# TwoMotorController_2_0.net
KiCad netlist of a schematic drawn in EAGLE
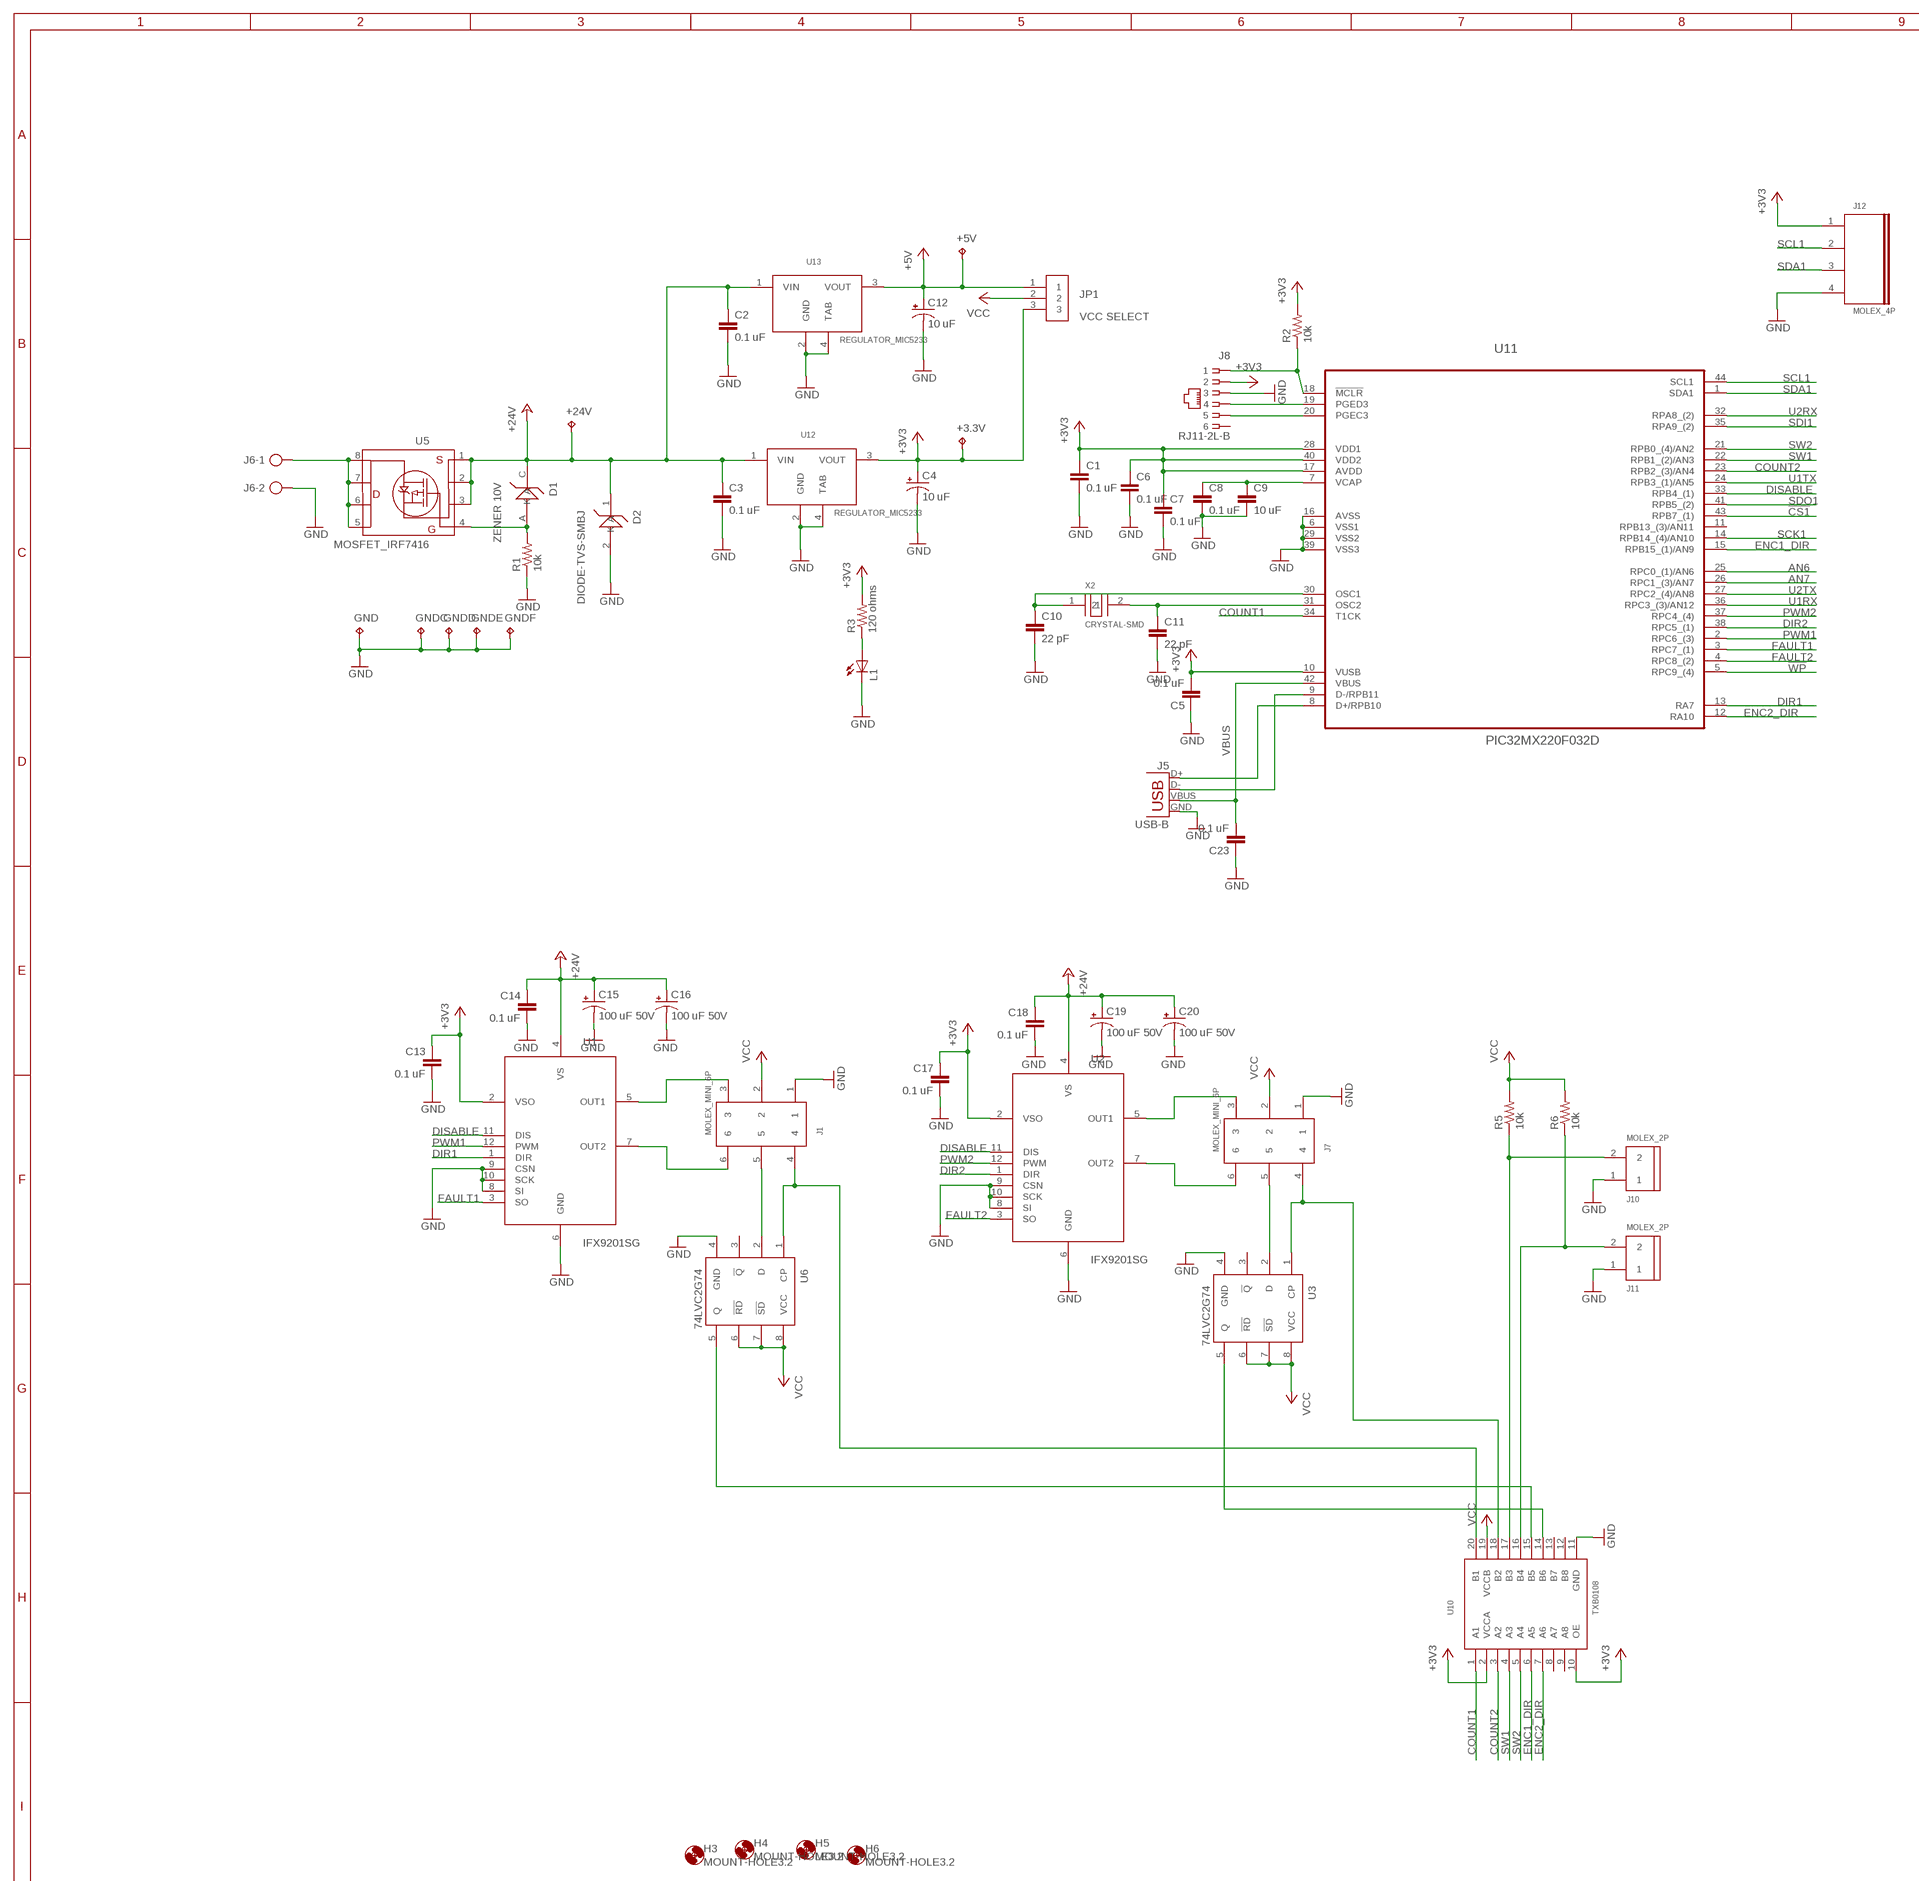
[diagram p0: schematic, sheet 1, part 1 of 2]
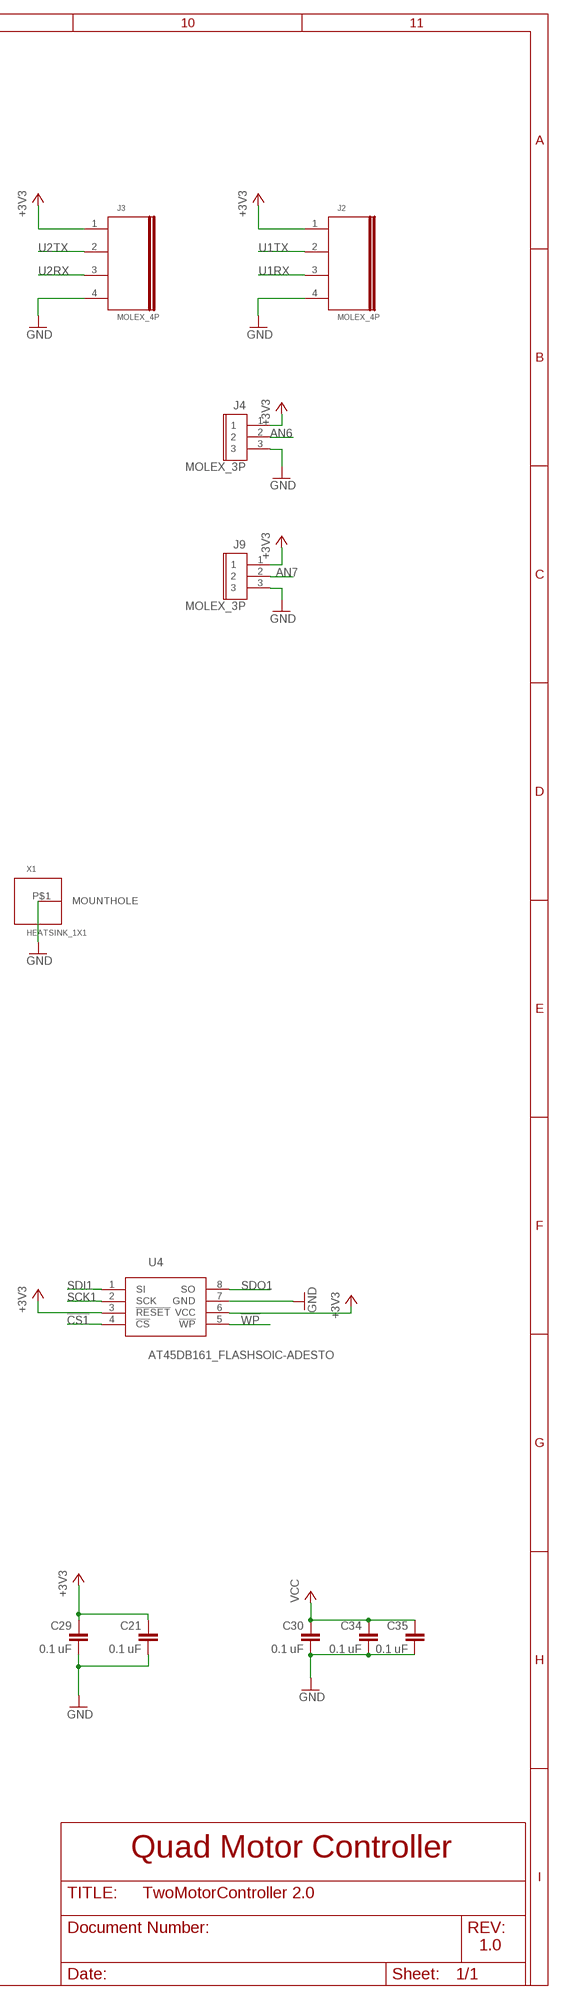
[diagram p1: schematic, sheet 1, part 2 of 2]

(export (version "E")
  (design (tool "Eeschema 10.0.6"))
  (components
    (comp (ref "+3.3V")
      (value "TP")
      (footprint "eagle-import:TESTPAD")
      (libsource (lib "eagle-import") (part "TP"))
    )
    (comp (ref "+5V")
      (value "TP")
      (footprint "eagle-import:TESTPAD")
      (libsource (lib "eagle-import") (part "TP"))
    )
    (comp (ref "+24V")
      (value "TP")
      (footprint "eagle-import:TESTPAD")
      (libsource (lib "eagle-import") (part "TP"))
    )
    (comp (ref "C1")
      (value "0.1 uF")
      (footprint "eagle-import:C0805")
      (libsource (lib "eagle-import") (part "C0805"))
    )
    (comp (ref "C2")
      (value "0.1 uF")
      (footprint "eagle-import:C0805")
      (libsource (lib "eagle-import") (part "C0805"))
    )
    (comp (ref "C3")
      (value "0.1 uF")
      (footprint "eagle-import:C0805")
      (libsource (lib "eagle-import") (part "C0805"))
    )
    (comp (ref "C4")
      (value "10 uF")
      (footprint "eagle-import:POLCAP_2MM")
      (libsource (lib "eagle-import") (part "POLCAPE2-5"))
    )
    (comp (ref "C5")
      (value "0.1 uF")
      (footprint "eagle-import:C2.5-3")
      (libsource (lib "eagle-import") (part "C2,5-3"))
    )
    (comp (ref "C6")
      (value "0.1 uF")
      (footprint "eagle-import:C0805")
      (libsource (lib "eagle-import") (part "C0805"))
    )
    (comp (ref "C7")
      (value "0.1 uF")
      (footprint "eagle-import:C0805")
      (libsource (lib "eagle-import") (part "C0805"))
    )
    (comp (ref "C8")
      (value "0.1 uF")
      (footprint "eagle-import:C0805")
      (libsource (lib "eagle-import") (part "C0805"))
    )
    (comp (ref "C9")
      (value "10 uF")
      (footprint "eagle-import:C0805")
      (libsource (lib "eagle-import") (part "C0805"))
    )
    (comp (ref "C10")
      (value "22 pF")
      (footprint "eagle-import:C0805")
      (libsource (lib "eagle-import") (part "C0805"))
    )
    (comp (ref "C11")
      (value "22 pF")
      (footprint "eagle-import:C0805")
      (libsource (lib "eagle-import") (part "C0805"))
    )
    (comp (ref "C12")
      (value "10 uF")
      (footprint "eagle-import:POLCAP_2MM")
      (libsource (lib "eagle-import") (part "POLCAPE2-5"))
    )
    (comp (ref "C13")
      (value "0.1 uF")
      (footprint "eagle-import:C0805")
      (libsource (lib "eagle-import") (part "C0805"))
    )
    (comp (ref "C14")
      (value "0.1 uF")
      (footprint "eagle-import:C0805")
      (libsource (lib "eagle-import") (part "C0805"))
    )
    (comp (ref "C15")
      (value "100 uF 50V")
      (footprint "eagle-import:E3,5-10")
      (libsource (lib "eagle-import") (part "POLCAPE3.5-10"))
    )
    (comp (ref "C16")
      (value "100 uF 50V")
      (footprint "eagle-import:E3,5-10")
      (libsource (lib "eagle-import") (part "POLCAPE3.5-10"))
    )
    (comp (ref "C17")
      (value "0.1 uF")
      (footprint "eagle-import:C0805")
      (libsource (lib "eagle-import") (part "C0805"))
    )
    (comp (ref "C18")
      (value "0.1 uF")
      (footprint "eagle-import:C0805")
      (libsource (lib "eagle-import") (part "C0805"))
    )
    (comp (ref "C19")
      (value "100 uF 50V")
      (footprint "eagle-import:E3,5-10")
      (libsource (lib "eagle-import") (part "POLCAPE3.5-10"))
    )
    (comp (ref "C20")
      (value "100 uF 50V")
      (footprint "eagle-import:E3,5-10")
      (libsource (lib "eagle-import") (part "POLCAPE3.5-10"))
    )
    (comp (ref "C21")
      (value "0.1 uF")
      (footprint "eagle-import:C0805")
      (libsource (lib "eagle-import") (part "C0805"))
    )
    (comp (ref "C23")
      (value "0.1 uF")
      (footprint "eagle-import:C2.5-3")
      (libsource (lib "eagle-import") (part "C2,5-3"))
    )
    (comp (ref "C29")
      (value "0.1 uF")
      (footprint "eagle-import:C0805")
      (libsource (lib "eagle-import") (part "C0805"))
    )
    (comp (ref "C30")
      (value "0.1 uF")
      (footprint "eagle-import:C0805")
      (libsource (lib "eagle-import") (part "C0805"))
    )
    (comp (ref "C34")
      (value "0.1 uF")
      (footprint "eagle-import:C0805")
      (libsource (lib "eagle-import") (part "C0805"))
    )
    (comp (ref "C35")
      (value "0.1 uF")
      (footprint "eagle-import:C0805")
      (libsource (lib "eagle-import") (part "C0805"))
    )
    (comp (ref "D1")
      (value "ZENER 10V")
      (footprint "eagle-import:DO-214AC")
      (libsource (lib "eagle-import") (part "DIODE-ZENERDO-214AC"))
    )
    (comp (ref "D2")
      (value "DIODE-TVS-SMBJ")
      (footprint "eagle-import:DIODE-TVS-SMBJ")
      (libsource (lib "eagle-import") (part "DIODE-TVS-SMBJ"))
    )
    (comp (ref "GND")
      (value "TP")
      (footprint "eagle-import:TESTPAD")
      (libsource (lib "eagle-import") (part "TP"))
    )
    (comp (ref "GNDC")
      (value "TP")
      (footprint "eagle-import:TESTPAD")
      (libsource (lib "eagle-import") (part "TP"))
    )
    (comp (ref "GNDD")
      (value "TP")
      (footprint "eagle-import:TESTPAD")
      (libsource (lib "eagle-import") (part "TP"))
    )
    (comp (ref "GNDE")
      (value "TP")
      (footprint "eagle-import:TESTPAD")
      (libsource (lib "eagle-import") (part "TP"))
    )
    (comp (ref "GNDF")
      (value "TP")
      (footprint "eagle-import:TESTPAD")
      (libsource (lib "eagle-import") (part "TP"))
    )
    (comp (ref "H3")
      (value "MOUNT-HOLE3.2")
      (footprint "eagle-import:3,2")
      (libsource (lib "eagle-import") (part "MOUNT-HOLE3.2"))
    )
    (comp (ref "H4")
      (value "MOUNT-HOLE3.2")
      (footprint "eagle-import:3,2")
      (libsource (lib "eagle-import") (part "MOUNT-HOLE3.2"))
    )
    (comp (ref "H5")
      (value "MOUNT-HOLE3.2")
      (footprint "eagle-import:3,2")
      (libsource (lib "eagle-import") (part "MOUNT-HOLE3.2"))
    )
    (comp (ref "H6")
      (value "MOUNT-HOLE3.2")
      (footprint "eagle-import:3,2")
      (libsource (lib "eagle-import") (part "MOUNT-HOLE3.2"))
    )
    (comp (ref "J1")
      (value "MOLEX_MINI_6P")
      (footprint "eagle-import:MOLEX_MINI_6P")
      (libsource (lib "eagle-import") (part "MOLEX_MINI_6P"))
    )
    (comp (ref "J2")
      (value "MOLEX_4P")
      (footprint "eagle-import:MOLEX_4P")
      (libsource (lib "eagle-import") (part "MOLEX_4P"))
    )
    (comp (ref "J3")
      (value "MOLEX_4P")
      (footprint "eagle-import:MOLEX_4P")
      (libsource (lib "eagle-import") (part "MOLEX_4P"))
    )
    (comp (ref "J4")
      (value "MOLEX_3P")
      (footprint "eagle-import:MOLEX_3P")
      (libsource (lib "eagle-import") (part "MOLEX_3P"))
    )
    (comp (ref "J5")
      (value "USB-B")
      (footprint "eagle-import:USB-B-PTH")
      (libsource (lib "eagle-import") (part "USBPTH"))
    )
    (comp (ref "J6")
      (value "TRMBLOCK_5MM_2P")
      (footprint "eagle-import:TRMBLOCK_5MM_2P")
      (libsource (lib "eagle-import") (part "TRMBLOCK_5MM_2P"))
    )
    (comp (ref "J7")
      (value "MOLEX_MINI_6P")
      (footprint "eagle-import:MOLEX_MINI_6P")
      (libsource (lib "eagle-import") (part "MOLEX_MINI_6P"))
    )
    (comp (ref "J8")
      (value "RJ11-2L-B")
      (footprint "eagle-import:RJ11-NO_SHIELD")
      (fields (field (name "MF") "TYCO ELECTRONICS"))
      (libsource (lib "eagle-import") (part "RJ11-2L-B"))
    )
    (comp (ref "J9")
      (value "MOLEX_3P")
      (footprint "eagle-import:MOLEX_3P")
      (libsource (lib "eagle-import") (part "MOLEX_3P"))
    )
    (comp (ref "J10")
      (value "MOLEX_2P")
      (footprint "eagle-import:MOLEX_2P")
      (libsource (lib "eagle-import") (part "MOLEX_2P"))
    )
    (comp (ref "J11")
      (value "MOLEX_2P")
      (footprint "eagle-import:MOLEX_2P")
      (libsource (lib "eagle-import") (part "MOLEX_2P"))
    )
    (comp (ref "J12")
      (value "MOLEX_4P")
      (footprint "eagle-import:MOLEX_4P")
      (libsource (lib "eagle-import") (part "MOLEX_4P"))
    )
    (comp (ref "JP1")
      (value "VCC SELECT")
      (footprint "eagle-import:JUMPER_3P")
      (libsource (lib "eagle-import") (part "JUMPER_3P"))
    )
    (comp (ref "L1")
      (value "LED5MM")
      (footprint "eagle-import:LED5MM")
      (libsource (lib "eagle-import") (part "LED5MM"))
    )
    (comp (ref "R1")
      (value "10k")
      (footprint "eagle-import:R0805")
      (libsource (lib "eagle-import") (part "RESISTORR0805"))
    )
    (comp (ref "R2")
      (value "10k")
      (footprint "eagle-import:R0805")
      (libsource (lib "eagle-import") (part "RESISTORR0805"))
    )
    (comp (ref "R3")
      (value "120 ohms")
      (footprint "eagle-import:R0805")
      (libsource (lib "eagle-import") (part "RESISTORR0805"))
    )
    (comp (ref "R5")
      (value "10k")
      (footprint "eagle-import:R0805")
      (libsource (lib "eagle-import") (part "RESISTORR0805"))
    )
    (comp (ref "R6")
      (value "10k")
      (footprint "eagle-import:R0805")
      (libsource (lib "eagle-import") (part "RESISTORR0805"))
    )
    (comp (ref "U1")
      (value "IFX9201SG")
      (footprint "eagle-import:IFX9201SG")
      (libsource (lib "eagle-import") (part "IFX9201SG"))
    )
    (comp (ref "U2")
      (value "IFX9201SG")
      (footprint "eagle-import:IFX9201SG")
      (libsource (lib "eagle-import") (part "IFX9201SG"))
    )
    (comp (ref "U3")
      (value "74LVC2G74")
      (footprint "eagle-import:TSSOP8")
      (libsource (lib "eagle-import") (part "74LVC2G74"))
    )
    (comp (ref "U4")
      (value "AT45DB161_FLASHSOIC-ADESTO")
      (footprint "eagle-import:SOIC-ADESTO")
      (libsource (lib "eagle-import") (part "AT45DB161_FLASHSOIC-ADESTO"))
    )
    (comp (ref "U5")
      (value "MOSFET_IRF7416")
      (footprint "eagle-import:SO-8-3.9MM")
      (libsource (lib "eagle-import") (part "MOSFET_IRF7416"))
    )
    (comp (ref "U6")
      (value "74LVC2G74")
      (footprint "eagle-import:TSSOP8")
      (libsource (lib "eagle-import") (part "74LVC2G74"))
    )
    (comp (ref "U10")
      (value "TXB0108")
      (footprint "eagle-import:TSSOP20")
      (libsource (lib "eagle-import") (part "TXB0108"))
    )
    (comp (ref "U11")
      (value "PIC32MX220F032D")
      (footprint "eagle-import:QFP80P1200X1200X120-44N")
      (fields (field (name "MPN") "PIC18F4550-I/PT"))
      (libsource (lib "eagle-import") (part "PIC32MX220F032D"))
    )
    (comp (ref "U12")
      (value "REGULATOR_MIC5233")
      (footprint "eagle-import:REGULATOR_MIC5233")
      (libsource (lib "eagle-import") (part "REGULATOR_MIC5233"))
    )
    (comp (ref "U13")
      (value "REGULATOR_MIC5233")
      (footprint "eagle-import:REGULATOR_MIC5233")
      (libsource (lib "eagle-import") (part "REGULATOR_MIC5233"))
    )
    (comp (ref "X1")
      (value "HEATSINK_1X1")
      (footprint "eagle-import:HEATSINK_1X1")
      (libsource (lib "eagle-import") (part "HEATSINK_1X1"))
    )
    (comp (ref "X2")
      (value "CRYSTAL-SMD")
      (footprint "eagle-import:CRYSTAL-SMD")
      (libsource (lib "eagle-import") (part "CRYSTAL-SMD"))
    )
  )
  (nets
    (net (code "1") (name "+3V3") (class "Default")
      (node (ref "+3.3V") (pin "P$1") (pinfunction "TP_P$1") (pintype "input"))
      (node (ref "C1") (pin "1") (pinfunction "1_1") (pintype "passive"))
      (node (ref "C13") (pin "1") (pinfunction "1_1") (pintype "passive"))
      (node (ref "C17") (pin "1") (pinfunction "1_1") (pintype "passive"))
      (node (ref "C21") (pin "1") (pinfunction "1_1") (pintype "passive"))
      (node (ref "C29") (pin "1") (pinfunction "1_1") (pintype "passive"))
      (node (ref "C4") (pin "+") (pinfunction "+_+") (pintype "passive"))
      (node (ref "C5") (pin "2") (pinfunction "2_2") (pintype "passive"))
      (node (ref "C6") (pin "1") (pinfunction "1_1") (pintype "passive"))
      (node (ref "C7") (pin "1") (pinfunction "1_1") (pintype "passive"))
      (node (ref "J12") (pin "1") (pinfunction "1_1") (pintype "bidirectional"))
      (node (ref "J2") (pin "1") (pinfunction "1_1") (pintype "bidirectional"))
      (node (ref "J3") (pin "1") (pinfunction "1_1") (pintype "bidirectional"))
      (node (ref "J4") (pin "1") (pinfunction "1_1") (pintype "bidirectional"))
      (node (ref "J8") (pin "2") (pinfunction "2_2") (pintype "passive"))
      (node (ref "J9") (pin "1") (pinfunction "1_1") (pintype "bidirectional"))
      (node (ref "JP1") (pin "3") (pinfunction "3_3") (pintype "bidirectional"))
      (node (ref "R2") (pin "2") (pinfunction "2_2") (pintype "passive"))
      (node (ref "R3") (pin "2") (pinfunction "2_2") (pintype "passive"))
      (node (ref "U1") (pin "2") (pinfunction "VSO_2") (pintype "bidirectional"))
      (node (ref "U10") (pin "10") (pinfunction "OE_10") (pintype "bidirectional"))
      (node (ref "U10") (pin "2") (pinfunction "VCCA_2") (pintype "bidirectional"))
      (node (ref "U11") (pin "10") (pinfunction "VUSB_10") (pintype "bidirectional"))
      (node (ref "U11") (pin "17") (pinfunction "AVDD_17") (pintype "power_in"))
      (node (ref "U11") (pin "28") (pinfunction "VDD1_28") (pintype "power_in"))
      (node (ref "U11") (pin "40") (pinfunction "VDD2_40") (pintype "input"))
      (node (ref "U12") (pin "3") (pinfunction "VOUT_3") (pintype "power_in"))
      (node (ref "U2") (pin "2") (pinfunction "VSO_2") (pintype "bidirectional"))
      (node (ref "U4") (pin "3") (pinfunction "~{RESET}_3") (pintype "input"))
      (node (ref "U4") (pin "6") (pinfunction "VCC_6") (pintype "power_in"))
    )
    (net (code "2") (name "+5V") (class "Default")
      (node (ref "+5V") (pin "P$1") (pinfunction "TP_P$1") (pintype "input"))
      (node (ref "C12") (pin "+") (pinfunction "+_+") (pintype "passive"))
      (node (ref "JP1") (pin "1") (pinfunction "1_1") (pintype "bidirectional"))
      (node (ref "U13") (pin "3") (pinfunction "VOUT_3") (pintype "power_in"))
    )
    (net (code "3") (name "+24V") (class "Default")
      (node (ref "+24V") (pin "P$1") (pinfunction "TP_P$1") (pintype "input"))
      (node (ref "C14") (pin "1") (pinfunction "1_1") (pintype "passive"))
      (node (ref "C15") (pin "+") (pinfunction "+_+") (pintype "passive"))
      (node (ref "C16") (pin "+") (pinfunction "+_+") (pintype "passive"))
      (node (ref "C18") (pin "1") (pinfunction "1_1") (pintype "passive"))
      (node (ref "C19") (pin "+") (pinfunction "+_+") (pintype "passive"))
      (node (ref "C2") (pin "1") (pinfunction "1_1") (pintype "passive"))
      (node (ref "C20") (pin "+") (pinfunction "+_+") (pintype "passive"))
      (node (ref "C3") (pin "1") (pinfunction "1_1") (pintype "passive"))
      (node (ref "D1") (pin "C") (pinfunction "K_C") (pintype "power_in"))
      (node (ref "D2") (pin "1") (pinfunction "K_1") (pintype "power_in"))
      (node (ref "U1") (pin "4") (pinfunction "VS_4") (pintype "power_in"))
      (node (ref "U12") (pin "1") (pinfunction "VIN_1") (pintype "power_in"))
      (node (ref "U13") (pin "1") (pinfunction "VIN_1") (pintype "power_in"))
      (node (ref "U2") (pin "4") (pinfunction "VS_4") (pintype "power_in"))
      (node (ref "U5") (pin "1") (pinfunction "P$1_1") (pintype "bidirectional"))
      (node (ref "U5") (pin "2") (pinfunction "P$2_2") (pintype "bidirectional"))
      (node (ref "U5") (pin "3") (pinfunction "P$3_3") (pintype "bidirectional"))
    )
    (net (code "4") (name "/AN6") (class "Default")
      (node (ref "J4") (pin "2") (pinfunction "2_2") (pintype "bidirectional"))
      (node (ref "U11") (pin "25") (pinfunction "RPC0_(1)/AN6_25") (pintype "bidirectional"))
    )
    (net (code "5") (name "/AN7") (class "Default")
      (node (ref "J9") (pin "2") (pinfunction "2_2") (pintype "bidirectional"))
      (node (ref "U11") (pin "26") (pinfunction "RPC1_(3)/AN7_26") (pintype "bidirectional"))
    )
    (net (code "6") (name "/COUNT1") (class "Default")
      (node (ref "U10") (pin "1") (pinfunction "A1_1") (pintype "bidirectional"))
      (node (ref "U11") (pin "34") (pinfunction "T1CK_34") (pintype "bidirectional"))
    )
    (net (code "7") (name "/COUNT2") (class "Default")
      (node (ref "U10") (pin "3") (pinfunction "A2_3") (pintype "bidirectional"))
      (node (ref "U11") (pin "23") (pinfunction "RPB2_(3)/AN4_23") (pintype "bidirectional"))
    )
    (net (code "8") (name "/DIR1") (class "Default")
      (node (ref "U1") (pin "1") (pinfunction "DIR_1") (pintype "input"))
      (node (ref "U11") (pin "13") (pinfunction "RA7_13") (pintype "bidirectional"))
    )
    (net (code "9") (name "/DIR2") (class "Default")
      (node (ref "U11") (pin "38") (pinfunction "RPC5_(1)_38") (pintype "bidirectional"))
      (node (ref "U2") (pin "1") (pinfunction "DIR_1") (pintype "input"))
    )
    (net (code "10") (name "/DISABLE") (class "Default")
      (node (ref "U1") (pin "11") (pinfunction "DIS_11") (pintype "input"))
      (node (ref "U11") (pin "33") (pinfunction "RPB4_(1)_33") (pintype "bidirectional"))
      (node (ref "U2") (pin "11") (pinfunction "DIS_11") (pintype "input"))
    )
    (net (code "11") (name "/ENC1_DIR") (class "Default")
      (node (ref "U10") (pin "6") (pinfunction "A5_6") (pintype "bidirectional"))
      (node (ref "U11") (pin "15") (pinfunction "RPB15_(1)/AN9_15") (pintype "bidirectional"))
    )
    (net (code "12") (name "/ENC2_DIR") (class "Default")
      (node (ref "U10") (pin "7") (pinfunction "A6_7") (pintype "bidirectional"))
      (node (ref "U11") (pin "12") (pinfunction "RA10_12") (pintype "bidirectional"))
    )
    (net (code "13") (name "/FAULT1") (class "Default")
      (node (ref "U1") (pin "3") (pinfunction "SO_3") (pintype "output"))
      (node (ref "U11") (pin "3") (pinfunction "RPC7_(1)_3") (pintype "bidirectional"))
    )
    (net (code "14") (name "/FAULT2") (class "Default")
      (node (ref "U11") (pin "4") (pinfunction "RPC8_(2)_4") (pintype "bidirectional"))
      (node (ref "U2") (pin "3") (pinfunction "SO_3") (pintype "output"))
    )
    (net (code "15") (name "/PWM1") (class "Default")
      (node (ref "U1") (pin "12") (pinfunction "PWM_12") (pintype "input"))
      (node (ref "U11") (pin "2") (pinfunction "RPC6_(3)_2") (pintype "bidirectional"))
    )
    (net (code "16") (name "/PWM2") (class "Default")
      (node (ref "U11") (pin "37") (pinfunction "RPC4_(4)_37") (pintype "bidirectional"))
      (node (ref "U2") (pin "12") (pinfunction "PWM_12") (pintype "input"))
    )
    (net (code "17") (name "/SCK1") (class "Default")
      (node (ref "U11") (pin "14") (pinfunction "RPB14_(4)/AN10_14") (pintype "bidirectional"))
      (node (ref "U4") (pin "2") (pinfunction "SCK_2") (pintype "input"))
    )
    (net (code "18") (name "/SCL1") (class "Default")
      (node (ref "J12") (pin "2") (pinfunction "2_2") (pintype "bidirectional"))
      (node (ref "U11") (pin "44") (pinfunction "SCL1_44") (pintype "bidirectional"))
    )
    (net (code "19") (name "/SDA1") (class "Default")
      (node (ref "J12") (pin "3") (pinfunction "3_3") (pintype "bidirectional"))
      (node (ref "U11") (pin "1") (pinfunction "SDA1_1") (pintype "bidirectional"))
    )
    (net (code "20") (name "/SDI1") (class "Default")
      (node (ref "U11") (pin "35") (pinfunction "RPA9_(2)_35") (pintype "bidirectional"))
      (node (ref "U4") (pin "1") (pinfunction "SI_1") (pintype "input"))
    )
    (net (code "21") (name "/SDO1") (class "Default")
      (node (ref "U11") (pin "41") (pinfunction "RPB5_(2)_41") (pintype "bidirectional"))
      (node (ref "U4") (pin "8") (pinfunction "SO_8") (pintype "output"))
    )
    (net (code "22") (name "/SW1") (class "Default")
      (node (ref "U10") (pin "4") (pinfunction "A3_4") (pintype "bidirectional"))
      (node (ref "U11") (pin "22") (pinfunction "RPB1_(2)/AN3_22") (pintype "bidirectional"))
    )
    (net (code "23") (name "/SW2") (class "Default")
      (node (ref "U10") (pin "5") (pinfunction "A4_5") (pintype "bidirectional"))
      (node (ref "U11") (pin "21") (pinfunction "RPB0_(4)/AN2_21") (pintype "bidirectional"))
    )
    (net (code "24") (name "/U1RX") (class "Default")
      (node (ref "J2") (pin "3") (pinfunction "3_3") (pintype "bidirectional"))
      (node (ref "U11") (pin "36") (pinfunction "RPC3_(3)/AN12_36") (pintype "bidirectional"))
    )
    (net (code "25") (name "/U1TX") (class "Default")
      (node (ref "J2") (pin "2") (pinfunction "2_2") (pintype "bidirectional"))
      (node (ref "U11") (pin "24") (pinfunction "RPB3_(1)/AN5_24") (pintype "bidirectional"))
    )
    (net (code "26") (name "/U2RX") (class "Default")
      (node (ref "J3") (pin "3") (pinfunction "3_3") (pintype "bidirectional"))
      (node (ref "U11") (pin "32") (pinfunction "RPA8_(2)_32") (pintype "bidirectional"))
    )
    (net (code "27") (name "/U2TX") (class "Default")
      (node (ref "J3") (pin "2") (pinfunction "2_2") (pintype "bidirectional"))
      (node (ref "U11") (pin "27") (pinfunction "RPC2_(4)/AN8_27") (pintype "bidirectional"))
    )
    (net (code "28") (name "/VBUS") (class "Default")
      (node (ref "C23") (pin "2") (pinfunction "2_2") (pintype "passive"))
      (node (ref "J5") (pin "VBUS") (pinfunction "VBUS_VBUS") (pintype "bidirectional"))
      (node (ref "U11") (pin "42") (pinfunction "VBUS_42") (pintype "bidirectional"))
    )
    (net (code "29") (name "/~{CS1}") (class "Default")
      (node (ref "U11") (pin "43") (pinfunction "RPB7_(1)_43") (pintype "bidirectional"))
      (node (ref "U4") (pin "4") (pinfunction "~{CS}_4") (pintype "input"))
    )
    (net (code "30") (name "/~{WP}") (class "Default")
      (node (ref "U11") (pin "5") (pinfunction "RPC9_(4)_5") (pintype "bidirectional"))
      (node (ref "U4") (pin "5") (pinfunction "~{WP}_5") (pintype "input"))
    )
    (net (code "31") (name "GND") (class "Default")
      (node (ref "C1") (pin "2") (pinfunction "2_2") (pintype "passive"))
      (node (ref "C10") (pin "2") (pinfunction "2_2") (pintype "passive"))
      (node (ref "C11") (pin "2") (pinfunction "2_2") (pintype "passive"))
      (node (ref "C12") (pin "-") (pinfunction "-_-") (pintype "passive"))
      (node (ref "C13") (pin "2") (pinfunction "2_2") (pintype "passive"))
      (node (ref "C14") (pin "2") (pinfunction "2_2") (pintype "passive"))
      (node (ref "C15") (pin "-") (pinfunction "-_-") (pintype "passive"))
      (node (ref "C16") (pin "-") (pinfunction "-_-") (pintype "passive"))
      (node (ref "C17") (pin "2") (pinfunction "2_2") (pintype "passive"))
      (node (ref "C18") (pin "2") (pinfunction "2_2") (pintype "passive"))
      (node (ref "C19") (pin "-") (pinfunction "-_-") (pintype "passive"))
      (node (ref "C2") (pin "2") (pinfunction "2_2") (pintype "passive"))
      (node (ref "C20") (pin "-") (pinfunction "-_-") (pintype "passive"))
      (node (ref "C21") (pin "2") (pinfunction "2_2") (pintype "passive"))
      (node (ref "C23") (pin "1") (pinfunction "1_1") (pintype "passive"))
      (node (ref "C29") (pin "2") (pinfunction "2_2") (pintype "passive"))
      (node (ref "C3") (pin "2") (pinfunction "2_2") (pintype "passive"))
      (node (ref "C30") (pin "2") (pinfunction "2_2") (pintype "passive"))
      (node (ref "C34") (pin "2") (pinfunction "2_2") (pintype "passive"))
      (node (ref "C35") (pin "2") (pinfunction "2_2") (pintype "passive"))
      (node (ref "C4") (pin "-") (pinfunction "-_-") (pintype "passive"))
      (node (ref "C5") (pin "1") (pinfunction "1_1") (pintype "passive"))
      (node (ref "C6") (pin "2") (pinfunction "2_2") (pintype "passive"))
      (node (ref "C7") (pin "2") (pinfunction "2_2") (pintype "passive"))
      (node (ref "C8") (pin "2") (pinfunction "2_2") (pintype "passive"))
      (node (ref "C9") (pin "2") (pinfunction "2_2") (pintype "passive"))
      (node (ref "D2") (pin "2") (pinfunction "A_2") (pintype "power_in"))
      (node (ref "GND") (pin "P$1") (pinfunction "TP_P$1") (pintype "input"))
      (node (ref "GNDC") (pin "P$1") (pinfunction "TP_P$1") (pintype "input"))
      (node (ref "GNDD") (pin "P$1") (pinfunction "TP_P$1") (pintype "input"))
      (node (ref "GNDE") (pin "P$1") (pinfunction "TP_P$1") (pintype "input"))
      (node (ref "GNDF") (pin "P$1") (pinfunction "TP_P$1") (pintype "input"))
      (node (ref "J1") (pin "1") (pinfunction "1_1") (pintype "bidirectional"))
      (node (ref "J10") (pin "1") (pinfunction "1_1") (pintype "bidirectional"))
      (node (ref "J11") (pin "1") (pinfunction "1_1") (pintype "bidirectional"))
      (node (ref "J12") (pin "4") (pinfunction "4_4") (pintype "bidirectional"))
      (node (ref "J2") (pin "4") (pinfunction "4_4") (pintype "bidirectional"))
      (node (ref "J3") (pin "4") (pinfunction "4_4") (pintype "bidirectional"))
      (node (ref "J4") (pin "3") (pinfunction "3_3") (pintype "bidirectional"))
      (node (ref "J5") (pin "GND") (pinfunction "GND_GND") (pintype "bidirectional"))
      (node (ref "J6") (pin "2") (pinfunction "KL_2") (pintype "passive"))
      (node (ref "J7") (pin "1") (pinfunction "1_1") (pintype "bidirectional"))
      (node (ref "J8") (pin "3") (pinfunction "3_3") (pintype "passive"))
      (node (ref "J9") (pin "3") (pinfunction "3_3") (pintype "bidirectional"))
      (node (ref "L1") (pin "K") (pinfunction "C_K") (pintype "passive"))
      (node (ref "R1") (pin "1") (pinfunction "1_1") (pintype "passive"))
      (node (ref "U1") (pin "10") (pinfunction "SCK_10") (pintype "input"))
      (node (ref "U1") (pin "6") (pinfunction "GND_6") (pintype "power_in"))
      (node (ref "U1") (pin "8") (pinfunction "SI_8") (pintype "input"))
      (node (ref "U1") (pin "9") (pinfunction "CSN_9") (pintype "input"))
      (node (ref "U10") (pin "11") (pinfunction "GND_11") (pintype "bidirectional"))
      (node (ref "U11") (pin "16") (pinfunction "AVSS_16") (pintype "bidirectional"))
      (node (ref "U11") (pin "29") (pinfunction "VSS2_29") (pintype "bidirectional"))
      (node (ref "U11") (pin "39") (pinfunction "VSS3_39") (pintype "bidirectional"))
      (node (ref "U11") (pin "6") (pinfunction "VSS1_6") (pintype "bidirectional"))
      (node (ref "U12") (pin "2") (pinfunction "GND_2") (pintype "power_in"))
      (node (ref "U12") (pin "4") (pinfunction "TAB_4") (pintype "power_in"))
      (node (ref "U13") (pin "2") (pinfunction "GND_2") (pintype "power_in"))
      (node (ref "U13") (pin "4") (pinfunction "TAB_4") (pintype "power_in"))
      (node (ref "U2") (pin "10") (pinfunction "SCK_10") (pintype "input"))
      (node (ref "U2") (pin "6") (pinfunction "GND_6") (pintype "power_in"))
      (node (ref "U2") (pin "8") (pinfunction "SI_8") (pintype "input"))
      (node (ref "U2") (pin "9") (pinfunction "CSN_9") (pintype "input"))
      (node (ref "U3") (pin "4") (pinfunction "GND_4") (pintype "power_in"))
      (node (ref "U4") (pin "7") (pinfunction "GND_7") (pintype "power_in"))
      (node (ref "U6") (pin "4") (pinfunction "GND_4") (pintype "power_in"))
      (node (ref "X1") (pin "P$1") (pinfunction "MOUNTHOLE_P$1") (pintype "bidirectional"))
    )
    (net (code "32") (name "Net-(J6A-KL)") (class "Default")
      (node (ref "J6") (pin "1") (pinfunction "KL_1") (pintype "passive"))
      (node (ref "U5") (pin "5") (pinfunction "P$5_5") (pintype "bidirectional"))
      (node (ref "U5") (pin "6") (pinfunction "P$6_6") (pintype "bidirectional"))
      (node (ref "U5") (pin "7") (pinfunction "P$7_7") (pintype "bidirectional"))
      (node (ref "U5") (pin "8") (pinfunction "P$8_8") (pintype "bidirectional"))
    )
    (net (code "33") (name "Net-(L1-PadA)") (class "Default")
      (node (ref "L1") (pin "A") (pinfunction "A_A") (pintype "passive"))
      (node (ref "R3") (pin "1") (pinfunction "1_1") (pintype "passive"))
    )
    (net (code "34") (name "Net-(U1-OUT1)") (class "Default")
      (node (ref "J1") (pin "3") (pinfunction "3_3") (pintype "bidirectional"))
      (node (ref "U1") (pin "5") (pinfunction "OUT1_5") (pintype "output"))
    )
    (net (code "35") (name "Net-(U1-OUT2)") (class "Default")
      (node (ref "J1") (pin "6") (pinfunction "6_6") (pintype "bidirectional"))
      (node (ref "U1") (pin "7") (pinfunction "OUT2_7") (pintype "output"))
    )
    (net (code "36") (name "Net-(U2-OUT1)") (class "Default")
      (node (ref "J7") (pin "3") (pinfunction "3_3") (pintype "bidirectional"))
      (node (ref "U2") (pin "5") (pinfunction "OUT1_5") (pintype "output"))
    )
    (net (code "37") (name "Net-(U2-OUT2)") (class "Default")
      (node (ref "J7") (pin "6") (pinfunction "6_6") (pintype "bidirectional"))
      (node (ref "U2") (pin "7") (pinfunction "OUT2_7") (pintype "output"))
    )
    (net (code "38") (name "Net-(U3-D)") (class "Default")
      (node (ref "J7") (pin "5") (pinfunction "5_5") (pintype "bidirectional"))
      (node (ref "U3") (pin "2") (pinfunction "D_2") (pintype "input"))
    )
    (net (code "39") (name "Net-(U5-P$4)") (class "Default")
      (node (ref "D1") (pin "A") (pinfunction "A_A") (pintype "power_in"))
      (node (ref "R1") (pin "2") (pinfunction "2_2") (pintype "passive"))
      (node (ref "U5") (pin "4") (pinfunction "P$4_4") (pintype "bidirectional"))
    )
    (net (code "40") (name "Net-(U6-D)") (class "Default")
      (node (ref "J1") (pin "5") (pinfunction "5_5") (pintype "bidirectional"))
      (node (ref "U6") (pin "2") (pinfunction "D_2") (pintype "input"))
    )
    (net (code "41") (name "Net-(U10-B1)") (class "Default")
      (node (ref "J1") (pin "4") (pinfunction "4_4") (pintype "bidirectional"))
      (node (ref "U10") (pin "20") (pinfunction "B1_20") (pintype "bidirectional"))
      (node (ref "U6") (pin "1") (pinfunction "CP_1") (pintype "input"))
    )
    (net (code "42") (name "Net-(U10-B2)") (class "Default")
      (node (ref "J7") (pin "4") (pinfunction "4_4") (pintype "bidirectional"))
      (node (ref "U10") (pin "18") (pinfunction "B2_18") (pintype "bidirectional"))
      (node (ref "U3") (pin "1") (pinfunction "CP_1") (pintype "input"))
    )
    (net (code "43") (name "Net-(U10-B3)") (class "Default")
      (node (ref "J10") (pin "2") (pinfunction "2_2") (pintype "bidirectional"))
      (node (ref "R5") (pin "1") (pinfunction "1_1") (pintype "passive"))
      (node (ref "U10") (pin "17") (pinfunction "B3_17") (pintype "bidirectional"))
    )
    (net (code "44") (name "Net-(U10-B4)") (class "Default")
      (node (ref "J11") (pin "2") (pinfunction "2_2") (pintype "bidirectional"))
      (node (ref "R6") (pin "1") (pinfunction "1_1") (pintype "passive"))
      (node (ref "U10") (pin "16") (pinfunction "B4_16") (pintype "bidirectional"))
    )
    (net (code "45") (name "Net-(U10-B5)") (class "Default")
      (node (ref "U10") (pin "15") (pinfunction "B5_15") (pintype "bidirectional"))
      (node (ref "U6") (pin "5") (pinfunction "Q_5") (pintype "output"))
    )
    (net (code "46") (name "Net-(U10-B6)") (class "Default")
      (node (ref "U10") (pin "14") (pinfunction "B6_14") (pintype "bidirectional"))
      (node (ref "U3") (pin "5") (pinfunction "Q_5") (pintype "output"))
    )
    (net (code "47") (name "Net-(U11-D+{slash}RPB10)") (class "Default")
      (node (ref "J5") (pin "D+") (pinfunction "D+_D+") (pintype "bidirectional"))
      (node (ref "U11") (pin "8") (pinfunction "D+/RPB10_8") (pintype "bidirectional"))
    )
    (net (code "48") (name "Net-(U11-D-{slash}RPB11)") (class "Default")
      (node (ref "J5") (pin "D-") (pinfunction "D-_D-") (pintype "bidirectional"))
      (node (ref "U11") (pin "9") (pinfunction "D-/RPB11_9") (pintype "bidirectional"))
    )
    (net (code "49") (name "Net-(U11-OSC1)") (class "Default")
      (node (ref "C10") (pin "1") (pinfunction "1_1") (pintype "passive"))
      (node (ref "U11") (pin "30") (pinfunction "OSC1_30") (pintype "bidirectional"))
      (node (ref "X2") (pin "1") (pinfunction "1_1") (pintype "bidirectional"))
    )
    (net (code "50") (name "Net-(U11-OSC2)") (class "Default")
      (node (ref "C11") (pin "1") (pinfunction "1_1") (pintype "passive"))
      (node (ref "U11") (pin "31") (pinfunction "OSC2_31") (pintype "bidirectional"))
      (node (ref "X2") (pin "2") (pinfunction "2_2") (pintype "bidirectional"))
    )
    (net (code "51") (name "Net-(U11-PGEC3)") (class "Default")
      (node (ref "J8") (pin "5") (pinfunction "5_5") (pintype "passive"))
      (node (ref "U11") (pin "20") (pinfunction "PGEC3_20") (pintype "bidirectional"))
    )
    (net (code "52") (name "Net-(U11-PGED3)") (class "Default")
      (node (ref "J8") (pin "4") (pinfunction "4_4") (pintype "passive"))
      (node (ref "U11") (pin "19") (pinfunction "PGED3_19") (pintype "bidirectional"))
    )
    (net (code "53") (name "Net-(U11-VCAP)") (class "Default")
      (node (ref "C8") (pin "1") (pinfunction "1_1") (pintype "passive"))
      (node (ref "C9") (pin "1") (pinfunction "1_1") (pintype "passive"))
      (node (ref "U11") (pin "7") (pinfunction "VCAP_7") (pintype "bidirectional"))
    )
    (net (code "54") (name "Net-(U11-~{MCLR})") (class "Default")
      (node (ref "J8") (pin "1") (pinfunction "1_1") (pintype "passive"))
      (node (ref "R2") (pin "1") (pinfunction "1_1") (pintype "passive"))
      (node (ref "U11") (pin "18") (pinfunction "~{MCLR}_18") (pintype "power_in"))
    )
    (net (code "55") (name "VCC") (class "Default")
      (node (ref "C30") (pin "1") (pinfunction "1_1") (pintype "passive"))
      (node (ref "C34") (pin "1") (pinfunction "1_1") (pintype "passive"))
      (node (ref "C35") (pin "1") (pinfunction "1_1") (pintype "passive"))
      (node (ref "J1") (pin "2") (pinfunction "2_2") (pintype "bidirectional"))
      (node (ref "J7") (pin "2") (pinfunction "2_2") (pintype "bidirectional"))
      (node (ref "JP1") (pin "2") (pinfunction "2_2") (pintype "bidirectional"))
      (node (ref "R5") (pin "2") (pinfunction "2_2") (pintype "passive"))
      (node (ref "R6") (pin "2") (pinfunction "2_2") (pintype "passive"))
      (node (ref "U10") (pin "19") (pinfunction "VCCB_19") (pintype "bidirectional"))
      (node (ref "U3") (pin "6") (pinfunction "~{RD}_6") (pintype "input"))
      (node (ref "U3") (pin "7") (pinfunction "~{SD}_7") (pintype "input"))
      (node (ref "U3") (pin "8") (pinfunction "VCC_8") (pintype "power_in"))
      (node (ref "U6") (pin "6") (pinfunction "~{RD}_6") (pintype "input"))
      (node (ref "U6") (pin "7") (pinfunction "~{SD}_7") (pintype "input"))
      (node (ref "U6") (pin "8") (pinfunction "VCC_8") (pintype "power_in"))
    )
    (net (code "56") (name "unconnected-(J8-Pad6)") (class "Default")
      (node (ref "J8") (pin "6") (pinfunction "6_6") (pintype "passive"))
    )
    (net (code "57") (name "unconnected-(U3-~{Q}-Pad3)") (class "Default")
      (node (ref "U3") (pin "3") (pinfunction "~{Q}_3") (pintype "output"))
    )
    (net (code "58") (name "unconnected-(U6-~{Q}-Pad3)") (class "Default")
      (node (ref "U6") (pin "3") (pinfunction "~{Q}_3") (pintype "output"))
    )
    (net (code "59") (name "unconnected-(U10-A7-Pad8)") (class "Default")
      (node (ref "U10") (pin "8") (pinfunction "A7_8") (pintype "bidirectional"))
    )
    (net (code "60") (name "unconnected-(U10-A8-Pad9)") (class "Default")
      (node (ref "U10") (pin "9") (pinfunction "A8_9") (pintype "bidirectional"))
    )
    (net (code "61") (name "unconnected-(U10-B7-Pad13)") (class "Default")
      (node (ref "U10") (pin "13") (pinfunction "B7_13") (pintype "bidirectional"))
    )
    (net (code "62") (name "unconnected-(U10-B8-Pad12)") (class "Default")
      (node (ref "U10") (pin "12") (pinfunction "B8_12") (pintype "bidirectional"))
    )
    (net (code "63") (name "unconnected-(U11-RPB13_(3){slash}AN11-Pad11)") (class "Default")
      (node (ref "U11") (pin "11") (pinfunction "RPB13_(3)/AN11_11") (pintype "bidirectional"))
    )
  )
)
